# pa.net
KiCad netlist of a schematic drawn in Altium Designer
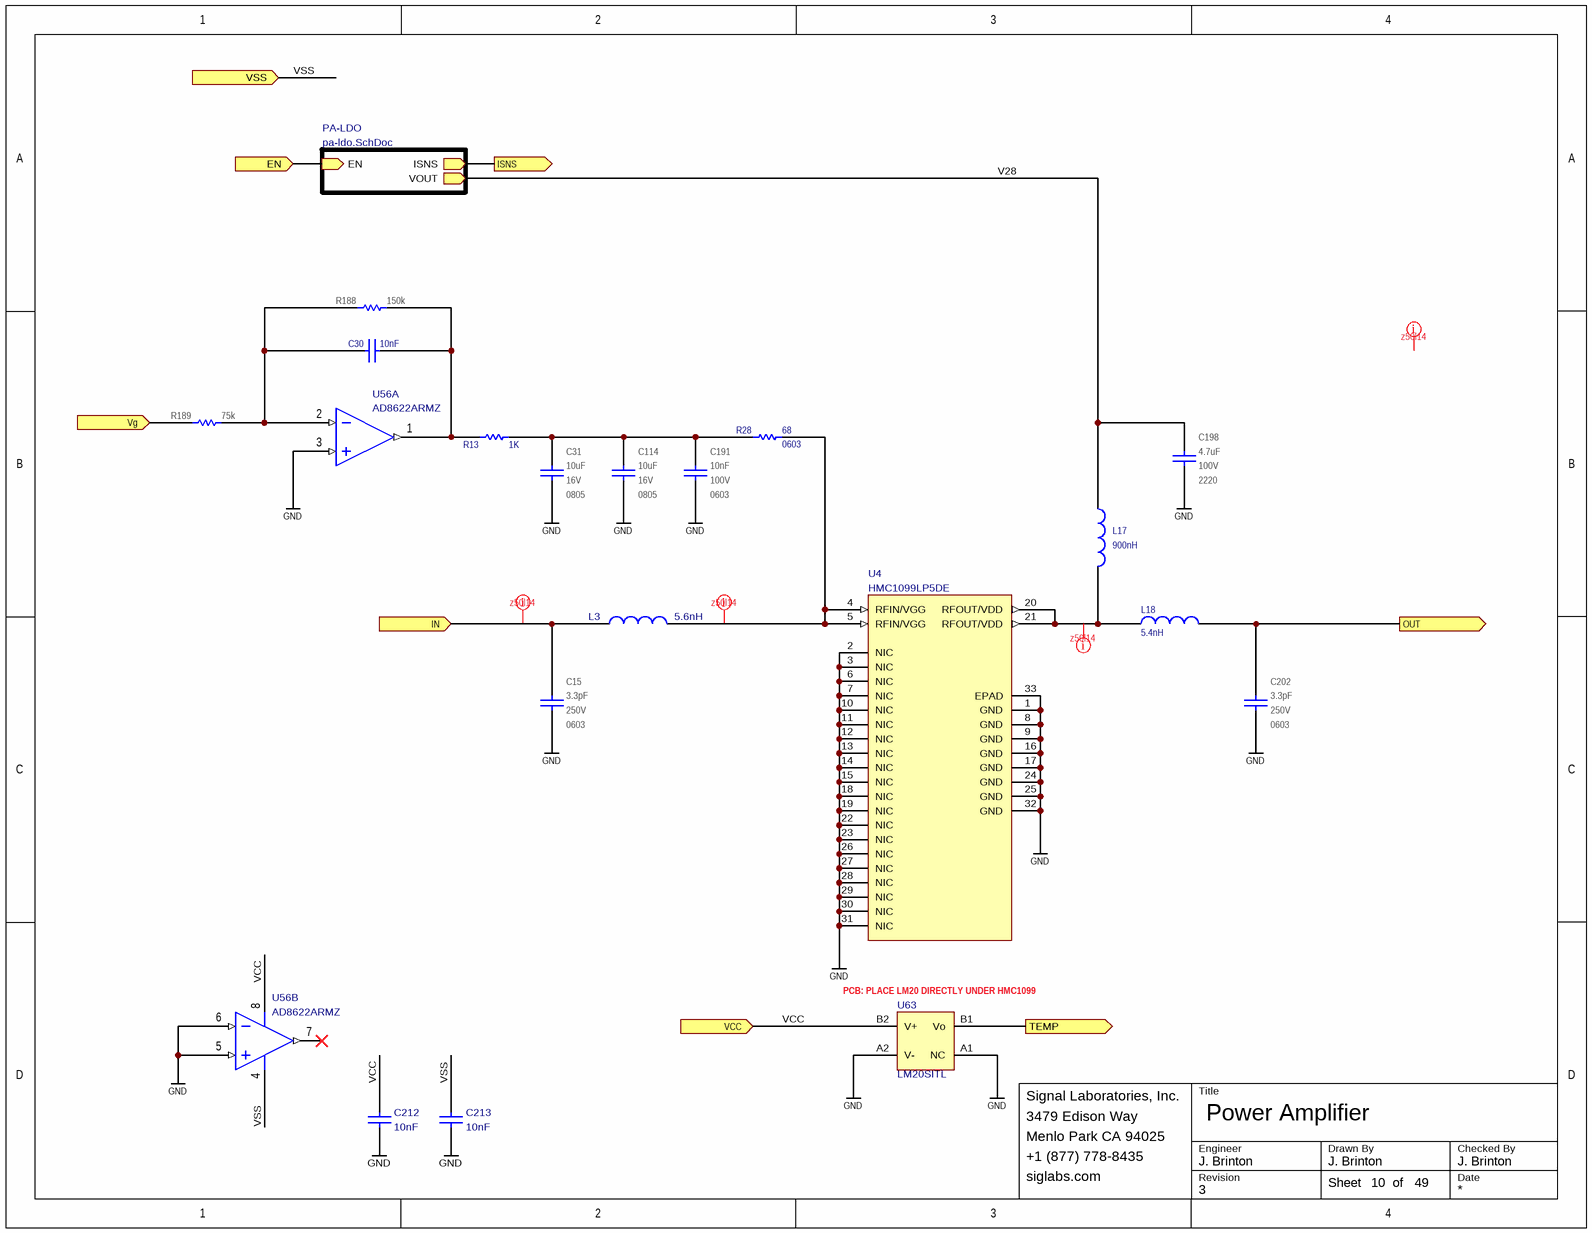
[diagram p0: pa.SchDoc]

(export (version "E")
  (design (tool "Eeschema 10.0.6"))
  (components
    (comp (ref "C15")
      (value "3.3pF")
      (footprint "generic:CAPC160X80X90L20N")
      (description "Ceramic Capacitor 3.3pF ±0.1pF 250V C0G 0603")
      (fields
        (field (name "MANUFACTURER") "Johanson Technology")
        (field (name "TOLERANCE") "±0.1pF")
        (field (name "VOLTAGE") "250V")
        (field (name "PACKAGE") "0603")
      )
      (libsource (lib "generic") (part "CAP"))
    )
    (comp (ref "C30")
      (value "10nF")
      (footprint "CAPC100X50X55L25N")
      (description "Ceramic Capacitor 10nF ±10% 50V X7R 0402")
      (fields (field (name "VOLTAGE") "50V") (field (name "MANUFACTURER") "Murata"))
      (libsource (lib "Graviton") (part "CAP 0402"))
    )
    (comp (ref "C31")
      (value "10uF")
      (footprint "CAPC2012X145N")
      (description "Ceramic Capacitor 10uF ±20% 16V X5R 0805")
      (fields
        (field (name "MANUFACTURER") "AVX")
        (field (name "TOLERANCE") "±20%")
        (field (name "VOLTAGE") "16V")
        (field (name "PACKAGE") "0805")
      )
      (libsource (lib "generic") (part "CAP"))
    )
    (comp (ref "C114")
      (value "10uF")
      (footprint "CAPC2012X145N")
      (description "Ceramic Capacitor 10uF ±20% 16V X5R 0805")
      (fields
        (field (name "MANUFACTURER") "AVX")
        (field (name "TOLERANCE") "±20%")
        (field (name "VOLTAGE") "16V")
        (field (name "PACKAGE") "0805")
      )
      (libsource (lib "generic") (part "CAP"))
    )
    (comp (ref "C191")
      (value "10nF")
      (footprint "CAPC1608X90N")
      (description "Ceramic Capacitor 10nF ±5% 100V X7R 0603")
      (fields
        (field (name "MANUFACTURER") "AVC")
        (field (name "TOLERANCE") "±5%")
        (field (name "VOLTAGE") "100V")
        (field (name "PACKAGE") "0603")
      )
      (libsource (lib "generic") (part "CAP"))
    )
    (comp (ref "C198")
      (value "4.7uF")
      (footprint "generic:CAPC570X500X230L57N")
      (description "Ceramic Capacitor 4.7uF ±10% 100V X7R 2220")
      (fields
        (field (name "MANUFACTURER") "TDK")
        (field (name "TOLERANCE") "±10%")
        (field (name "VOLTAGE") "100V")
        (field (name "PACKAGE") "2220")
      )
      (libsource (lib "generic") (part "CAP"))
    )
    (comp (ref "C202")
      (value "3.3pF")
      (footprint "generic:CAPC160X80X90L20N")
      (description "Ceramic Capacitor 3.3pF ±0.1pF 250V C0G 0603")
      (fields
        (field (name "MANUFACTURER") "Johanson Technology")
        (field (name "TOLERANCE") "±0.1pF")
        (field (name "VOLTAGE") "250V")
        (field (name "PACKAGE") "0603")
      )
      (libsource (lib "generic") (part "CAP"))
    )
    (comp (ref "C212")
      (value "10nF")
      (footprint "CAPC100X50X55L25N")
      (description "Ceramic Capacitor 10nF ±10% 50V X7R 0402")
      (fields (field (name "MANUFACTURER") "Murata") (field (name "TOLERANCE") "±10%"))
      (libsource (lib "capacitors") (part "CAP"))
    )
    (comp (ref "C213")
      (value "10nF")
      (footprint "CAPC100X50X55L25N")
      (description "Ceramic Capacitor 10nF ±10% 50V X7R 0402")
      (fields (field (name "MANUFACTURER") "Murata") (field (name "TOLERANCE") "±10%"))
      (libsource (lib "capacitors") (part "CAP"))
    )
    (comp (ref "L3")
      (value "5.6nH")
      (footprint "generic:INDC1005X55N")
      (description "Inductor 5.6nH ±0.2nH 650mA")
      (fields (field (name "MANUFACTURER") "Murata") (field (name "Comment") "LQG15HS5N6C02D"))
      (libsource (lib "generic") (part "INDUCTOR"))
    )
    (comp (ref "L17")
      (value "900nH")
      (footprint "coilcraft:COILCRAFT_1008AF")
      (description "Inductor 900nH ±5% 1008")
      (fields (field (name "MANUFACTURER") "Coilcraft") (field (name "TOLERANCE") "±5%"))
      (libsource (lib "generic") (part "INDUCTOR"))
    )
    (comp (ref "L18")
      (value "5.4nH")
      (footprint "coilcraft:0906-5L")
      (description "Inductor 5.4nH ±2% SMD")
      (fields (field (name "MANUFACTURER") "Coilcraft") (field (name "TOLERANCE") "±2%"))
      (libsource (lib "generic") (part "INDUCTOR"))
    )
    (comp (ref "R13")
      (value "1K")
      (footprint "RESC1005X40N")
      (description "Thick Film Resistor 1k ±1% 0402")
      (fields (field (name "MANUFACTURER") "Yageo") (field (name "TOLERANCE") "±1%"))
      (libsource (lib "Graviton") (part "RES 0402"))
    )
    (comp (ref "R28")
      (value "68")
      (footprint "generic:RESC1608X55N")
      (description "Thick Film 68 ±1% 0603")
      (fields
        (field (name "PACKAGE") "0603")
        (field (name "MANUFACTURER") "Vishay")
        (field (name "TOLERANCE") "±1%")
      )
      (libsource (lib "Graviton") (part "RES 0402"))
    )
    (comp (ref "R188")
      (value "150k")
      (footprint "RESC1005X40N")
      (description "Thick Film Resistor 150k ±1% 0.1W 50V 0402")
      (fields (field (name "MANUFACTURER") "Panasonic") (field (name "TOLERANCE") "±1%"))
      (libsource (lib "generic") (part "RES"))
    )
    (comp (ref "R189")
      (value "75k")
      (footprint "RESC1005X40N")
      (description "Thick Film Resistor 75k ±1% 0.1W 50V 0402")
      (fields (field (name "MANUFACTURER") "Panasonic") (field (name "TOLERANCE") "±1%"))
      (libsource (lib "generic") (part "RES"))
    )
    (comp (ref "U4")
      (value "HMC1099LP5DE")
      (footprint "QFN50P500X500X153-33N")
      (description "RF Amp Chip Single Power Amplifier 1.1GHz 32V 32-Pin QFN")
      (fields (field (name "MF") "Analog Devices"))
      (libsource (lib "analog_devices") (part "HMC1099LP5DE"))
    )
    (comp (ref "U56")
      (value "AD8622ARMZ")
      (footprint "generic:MSOP8")
      (description "Low Power, Precision Rail-to-Rail Output Op Amp MSOP")
      (fields (field (name "MANUFACTURER") "Analog Devices"))
      (libsource (lib "analog_devices") (part "AD8022"))
    )
    (comp (ref "U63")
      (value "LM20SITL")
      (footprint "YZR-4")
      (description "Analog Temperature Sensor")
      (fields (field (name "MANUFACTURER") "Texas Instruments"))
      (libsource (lib "ti") (part "LM20SITL"))
    )
  )
  (nets
    (net (code "2") (name "/IN") (class "Default")
      (node (ref "C15") (pin "2") (pinfunction "2_2") (pintype "passive"))
      (node (ref "L3") (pin "1") (pinfunction "1_1") (pintype "passive"))
    )
    (net (code "4") (name "/OUT") (class "Default")
      (node (ref "C202") (pin "2") (pinfunction "2_2") (pintype "passive"))
      (node (ref "L18") (pin "2") (pinfunction "2_2") (pintype "passive"))
    )
    (net (code "5") (name "/TEMP") (class "Default")
      (node (ref "U63") (pin "B1") (pinfunction "Vo_B1") (pintype "passive"))
    )
    (net (code "6") (name "/V28") (class "Default")
      (node (ref "C198") (pin "2") (pinfunction "2_2") (pintype "passive"))
      (node (ref "L17") (pin "1") (pinfunction "1_1") (pintype "passive"))
    )
    (net (code "7") (name "/VCC") (class "Default")
      (node (ref "C212") (pin "1") (pinfunction "1_1") (pintype "passive"))
      (node (ref "U56") (pin "8") (pinfunction "V+_8") (pintype "power_in"))
      (node (ref "U63") (pin "B2") (pinfunction "V+_B2") (pintype "passive"))
    )
    (net (code "8") (name "/VSS") (class "Default")
      (node (ref "C213") (pin "1") (pinfunction "1_1") (pintype "passive"))
      (node (ref "U56") (pin "4") (pinfunction "V-_4") (pintype "power_in"))
    )
    (net (code "9") (name "/Vg") (class "Default")
      (node (ref "R189") (pin "2") (pinfunction "2_2") (pintype "passive"))
    )
    (net (code "10") (name "GND") (class "Default")
      (node (ref "C114") (pin "1") (pinfunction "1_1") (pintype "passive"))
      (node (ref "C15") (pin "1") (pinfunction "1_1") (pintype "passive"))
      (node (ref "C191") (pin "1") (pinfunction "1_1") (pintype "passive"))
      (node (ref "C198") (pin "1") (pinfunction "1_1") (pintype "passive"))
      (node (ref "C202") (pin "1") (pinfunction "1_1") (pintype "passive"))
      (node (ref "C212") (pin "2") (pinfunction "2_2") (pintype "passive"))
      (node (ref "C213") (pin "2") (pinfunction "2_2") (pintype "passive"))
      (node (ref "C31") (pin "1") (pinfunction "1_1") (pintype "passive"))
      (node (ref "U4") (pin "1") (pinfunction "GND_1") (pintype "power_in"))
      (node (ref "U4") (pin "10") (pinfunction "NIC_10") (pintype "passive"))
      (node (ref "U4") (pin "11") (pinfunction "NIC_11") (pintype "passive"))
      (node (ref "U4") (pin "12") (pinfunction "NIC_12") (pintype "passive"))
      (node (ref "U4") (pin "13") (pinfunction "NIC_13") (pintype "passive"))
      (node (ref "U4") (pin "14") (pinfunction "NIC_14") (pintype "passive"))
      (node (ref "U4") (pin "15") (pinfunction "NIC_15") (pintype "passive"))
      (node (ref "U4") (pin "16") (pinfunction "GND_16") (pintype "power_in"))
      (node (ref "U4") (pin "17") (pinfunction "GND_17") (pintype "power_in"))
      (node (ref "U4") (pin "18") (pinfunction "NIC_18") (pintype "passive"))
      (node (ref "U4") (pin "19") (pinfunction "NIC_19") (pintype "passive"))
      (node (ref "U4") (pin "2") (pinfunction "NIC_2") (pintype "passive"))
      (node (ref "U4") (pin "22") (pinfunction "NIC_22") (pintype "passive"))
      (node (ref "U4") (pin "23") (pinfunction "NIC_23") (pintype "passive"))
      (node (ref "U4") (pin "24") (pinfunction "GND_24") (pintype "power_in"))
      (node (ref "U4") (pin "25") (pinfunction "GND_25") (pintype "power_in"))
      (node (ref "U4") (pin "26") (pinfunction "NIC_26") (pintype "passive"))
      (node (ref "U4") (pin "27") (pinfunction "NIC_27") (pintype "passive"))
      (node (ref "U4") (pin "28") (pinfunction "NIC_28") (pintype "passive"))
      (node (ref "U4") (pin "29") (pinfunction "NIC_29") (pintype "passive"))
      (node (ref "U4") (pin "3") (pinfunction "NIC_3") (pintype "passive"))
      (node (ref "U4") (pin "30") (pinfunction "NIC_30") (pintype "passive"))
      (node (ref "U4") (pin "31") (pinfunction "NIC_31") (pintype "passive"))
      (node (ref "U4") (pin "32") (pinfunction "GND_32") (pintype "power_in"))
      (node (ref "U4") (pin "33") (pinfunction "EPAD_33") (pintype "power_in"))
      (node (ref "U4") (pin "6") (pinfunction "NIC_6") (pintype "passive"))
      (node (ref "U4") (pin "7") (pinfunction "NIC_7") (pintype "passive"))
      (node (ref "U4") (pin "8") (pinfunction "GND_8") (pintype "power_in"))
      (node (ref "U4") (pin "9") (pinfunction "GND_9") (pintype "power_in"))
      (node (ref "U56") (pin "3") (pinfunction "IN+_3") (pintype "input"))
      (node (ref "U56") (pin "5") (pinfunction "IN+_5") (pintype "input"))
      (node (ref "U56") (pin "6") (pinfunction "IN-_6") (pintype "input"))
      (node (ref "U63") (pin "A1") (pinfunction "NC_A1") (pintype "passive"))
      (node (ref "U63") (pin "A2") (pinfunction "V-_A2") (pintype "passive"))
    )
    (net (code "11") (name "Net-(C114-Pad2)") (class "Default")
      (node (ref "C114") (pin "2") (pinfunction "2_2") (pintype "passive"))
      (node (ref "C191") (pin "2") (pinfunction "2_2") (pintype "passive"))
      (node (ref "C31") (pin "2") (pinfunction "2_2") (pintype "passive"))
      (node (ref "R13") (pin "1") (pinfunction "1_1") (pintype "passive"))
      (node (ref "R28") (pin "1") (pinfunction "1_1") (pintype "passive"))
    )
    (net (code "12") (name "Net-(L3-Pad2)") (class "Default")
      (node (ref "L3") (pin "2") (pinfunction "2_2") (pintype "passive"))
      (node (ref "R28") (pin "2") (pinfunction "2_2") (pintype "passive"))
      (node (ref "U4") (pin "4") (pinfunction "RFIN/VGG_4") (pintype "input"))
      (node (ref "U4") (pin "5") (pinfunction "RFIN/VGG_5") (pintype "input"))
    )
    (net (code "13") (name "Net-(L17-Pad2)") (class "Default")
      (node (ref "L17") (pin "2") (pinfunction "2_2") (pintype "passive"))
      (node (ref "L18") (pin "1") (pinfunction "1_1") (pintype "passive"))
      (node (ref "U4") (pin "20") (pinfunction "RFOUT/VDD_20") (pintype "output"))
      (node (ref "U4") (pin "21") (pinfunction "RFOUT/VDD_21") (pintype "output"))
    )
    (net (code "14") (name "Net-(U56A-IN-)") (class "Default")
      (node (ref "C30") (pin "2") (pinfunction "2_2") (pintype "passive"))
      (node (ref "R188") (pin "2") (pinfunction "2_2") (pintype "passive"))
      (node (ref "R189") (pin "1") (pinfunction "1_1") (pintype "passive"))
      (node (ref "U56") (pin "2") (pinfunction "IN-_2") (pintype "input"))
    )
    (net (code "15") (name "Net-(U56A-OUT)") (class "Default")
      (node (ref "C30") (pin "1") (pinfunction "1_1") (pintype "passive"))
      (node (ref "R13") (pin "2") (pinfunction "2_2") (pintype "passive"))
      (node (ref "R188") (pin "1") (pinfunction "1_1") (pintype "passive"))
      (node (ref "U56") (pin "1") (pinfunction "OUT_1") (pintype "output"))
    )
    (net (code "16") (name "unconnected-(U56B-OUT-Pad7)") (class "Default")
      (node (ref "U56") (pin "7") (pinfunction "OUT_7") (pintype "output+no_connect"))
    )
  )
)
